# RF_Glow_Stick.net
KiCad netlist of a schematic drawn in EAGLE
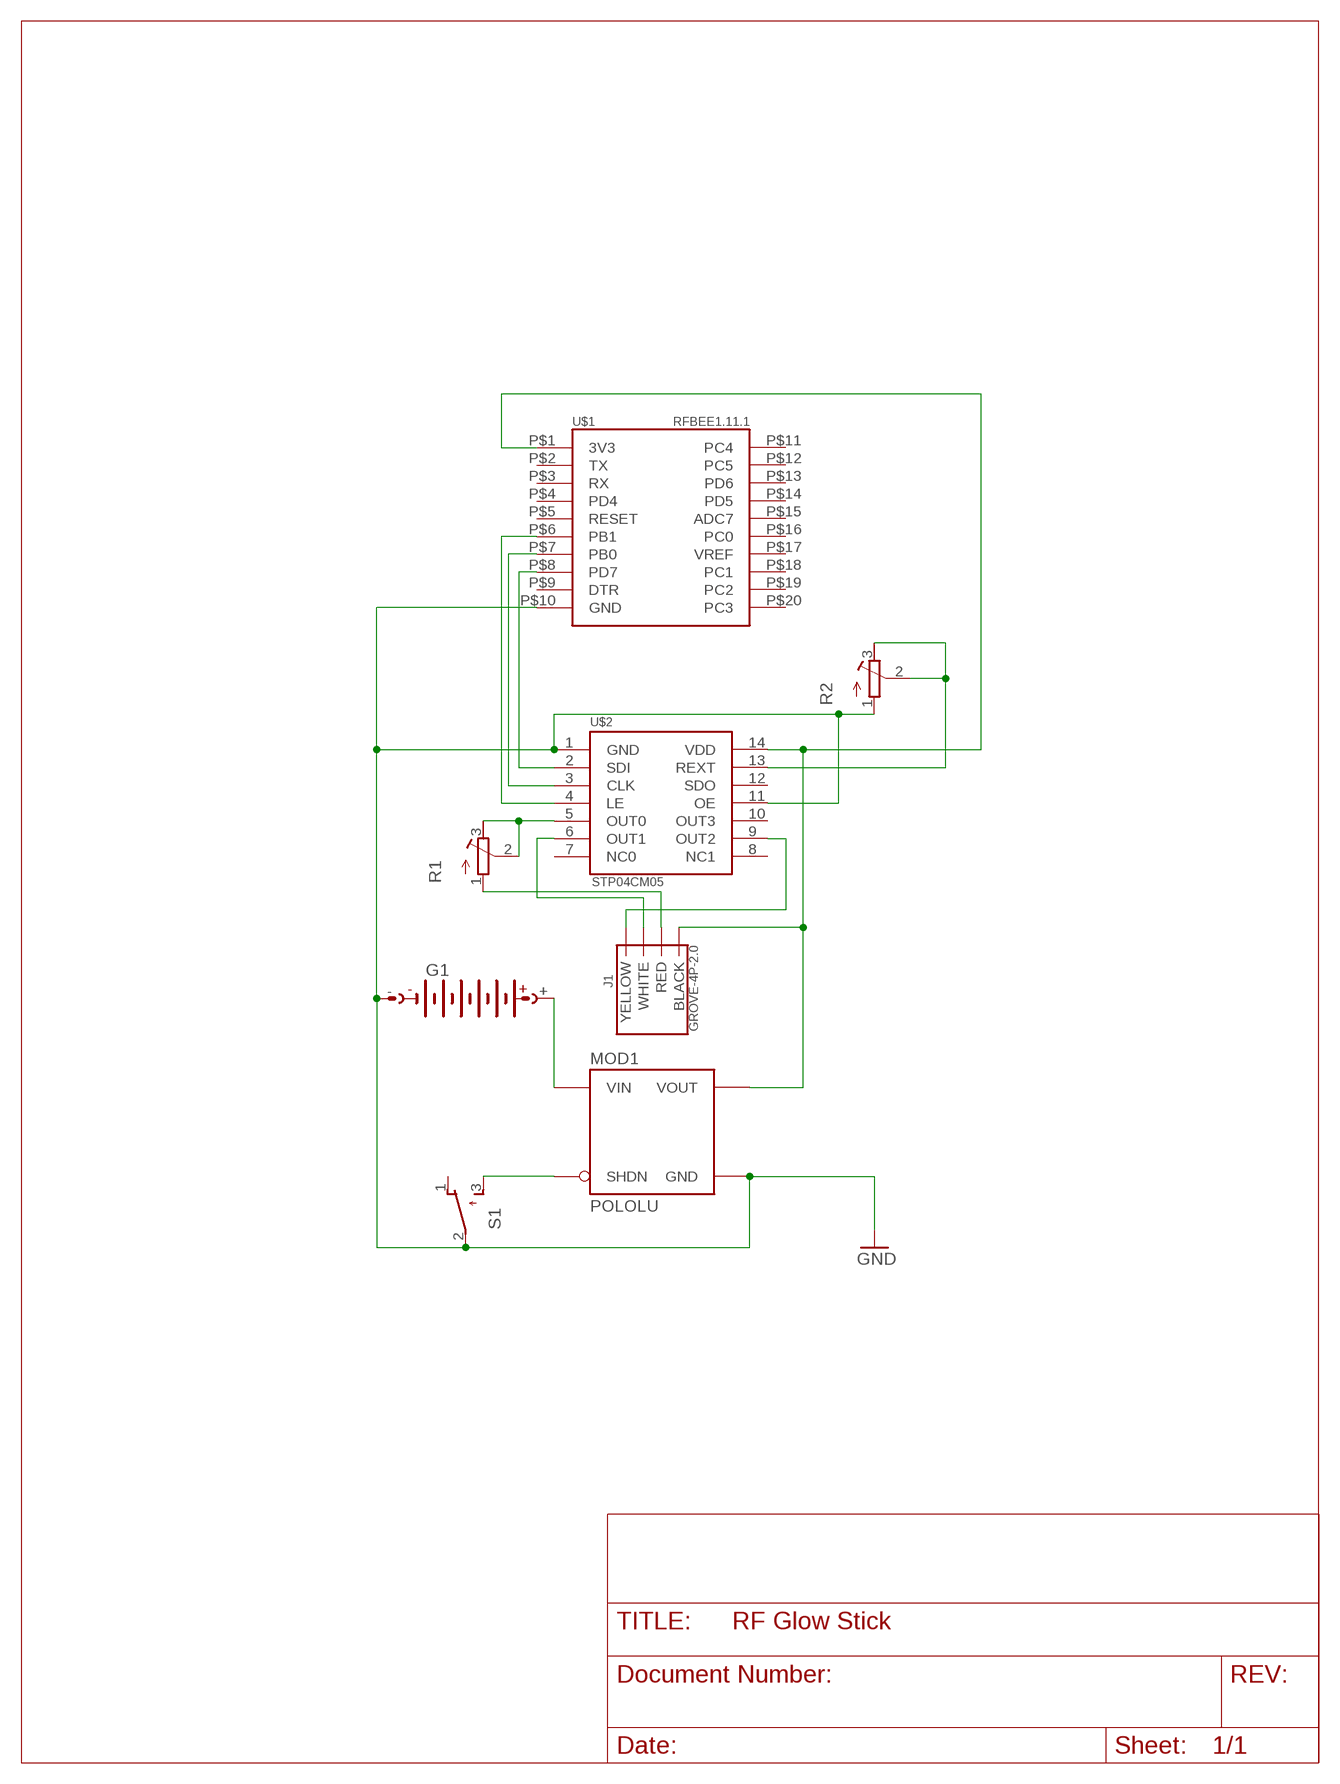
[diagram p0: schematic, sheet 1]

(export (version "E")
  (design (tool "Eeschema 10.0.6"))
  (components
    (comp (ref "G1")
      (value "AB9V")
      (footprint "eagle-import:AB9V")
      (libsource (lib "eagle-import") (part "AB9V"))
    )
    (comp (ref "J1")
      (value "GROVE-4P-2.0")
      (footprint "eagle-import:4P-2.0-90D")
      (libsource (lib "eagle-import") (part "GROVE-4P-2.0"))
    )
    (comp (ref "MOD1")
      (value "POLOLU")
      (footprint "eagle-import:POLOLU_REG09B")
      (libsource (lib "eagle-import") (part "POLOLU_REG09BV"))
    )
    (comp (ref "R1")
      (value "R-TRIMM3299W")
      (footprint "eagle-import:RTRIM3299W")
      (libsource (lib "eagle-import") (part "R-TRIMM3299W"))
    )
    (comp (ref "R2")
      (value "R-TRIMM3299W")
      (footprint "eagle-import:RTRIM3299W")
      (libsource (lib "eagle-import") (part "R-TRIMM3299W"))
    )
    (comp (ref "S1")
      (value "TL32PO")
      (footprint "eagle-import:TL3XPO")
      (libsource (lib "eagle-import") (part "TL32PO"))
    )
    (comp (ref "U$1")
      (value "RFBEE1.11.1")
      (footprint "eagle-import:RFBEE")
      (libsource (lib "eagle-import") (part "RFBEE1.11.1"))
    )
    (comp (ref "U$2")
      (value "STP04CM05")
      (footprint "eagle-import:DIL14")
      (libsource (lib "eagle-import") (part "STP04CM05STP04CM05"))
    )
  )
  (nets
    (net (code "1") (name "GND") (class "Default")
      (node (ref "G1") (pin "-") (pinfunction "-_-") (pintype "passive"))
      (node (ref "MOD1") (pin "G") (pinfunction "GND_G") (pintype "power_in"))
      (node (ref "R2") (pin "1") (pinfunction "A_1") (pintype "passive"))
      (node (ref "S1") (pin "2") (pinfunction "P_2") (pintype "passive"))
      (node (ref "U$1") (pin "P$10") (pinfunction "GND_P$10") (pintype "bidirectional"))
      (node (ref "U$2") (pin "1") (pinfunction "GND_1") (pintype "bidirectional"))
      (node (ref "U$2") (pin "11") (pinfunction "OE_11") (pintype "bidirectional"))
    )
    (net (code "2") (name "Net-(MOD1-SHDN)") (class "Default")
      (node (ref "MOD1") (pin "S") (pinfunction "SHDN_S") (pintype "input"))
      (node (ref "S1") (pin "3") (pinfunction "S_3") (pintype "passive"))
    )
    (net (code "3") (name "Net-(MOD1-VIN)") (class "Default")
      (node (ref "G1") (pin "+") (pinfunction "+_+") (pintype "passive"))
      (node (ref "MOD1") (pin "I") (pinfunction "VIN_I") (pintype "power_in"))
    )
    (net (code "4") (name "Net-(MOD1-VOUT)") (class "Default")
      (node (ref "J1") (pin "BLACK") (pinfunction "BLACK_BLACK") (pintype "bidirectional"))
      (node (ref "MOD1") (pin "O") (pinfunction "VOUT_O") (pintype "output"))
      (node (ref "U$1") (pin "P$1") (pinfunction "3V3_P$1") (pintype "bidirectional"))
      (node (ref "U$2") (pin "14") (pinfunction "VDD_14") (pintype "bidirectional"))
    )
    (net (code "5") (name "Net-(R1-A)") (class "Default")
      (node (ref "J1") (pin "RED") (pinfunction "RED_RED") (pintype "bidirectional"))
      (node (ref "R1") (pin "1") (pinfunction "A_1") (pintype "passive"))
    )
    (net (code "6") (name "Net-(R1-E)") (class "Default")
      (node (ref "R1") (pin "2") (pinfunction "S_2") (pintype "passive"))
      (node (ref "R1") (pin "3") (pinfunction "E_3") (pintype "passive"))
      (node (ref "U$2") (pin "5") (pinfunction "OUT0_5") (pintype "bidirectional"))
    )
    (net (code "7") (name "Net-(R2-E)") (class "Default")
      (node (ref "R2") (pin "2") (pinfunction "S_2") (pintype "passive"))
      (node (ref "R2") (pin "3") (pinfunction "E_3") (pintype "passive"))
      (node (ref "U$2") (pin "13") (pinfunction "REXT_13") (pintype "bidirectional"))
    )
    (net (code "8") (name "Net-(U$1-PB0)") (class "Default")
      (node (ref "U$1") (pin "P$7") (pinfunction "PB0_P$7") (pintype "bidirectional"))
      (node (ref "U$2") (pin "3") (pinfunction "CLK_3") (pintype "bidirectional"))
    )
    (net (code "9") (name "Net-(U$1-PB1)") (class "Default")
      (node (ref "U$1") (pin "P$6") (pinfunction "PB1_P$6") (pintype "bidirectional"))
      (node (ref "U$2") (pin "4") (pinfunction "LE_4") (pintype "bidirectional"))
    )
    (net (code "10") (name "Net-(U$1-PD7)") (class "Default")
      (node (ref "U$1") (pin "P$8") (pinfunction "PD7_P$8") (pintype "bidirectional"))
      (node (ref "U$2") (pin "2") (pinfunction "SDI_2") (pintype "bidirectional"))
    )
    (net (code "11") (name "Net-(U$2-OUT1)") (class "Default")
      (node (ref "J1") (pin "WHITE") (pinfunction "WHITE_WHITE") (pintype "bidirectional"))
      (node (ref "U$2") (pin "6") (pinfunction "OUT1_6") (pintype "bidirectional"))
    )
    (net (code "12") (name "Net-(U$2-OUT2)") (class "Default")
      (node (ref "J1") (pin "YELLOW") (pinfunction "YELLOW_YELLOW") (pintype "bidirectional"))
      (node (ref "U$2") (pin "9") (pinfunction "OUT2_9") (pintype "bidirectional"))
    )
    (net (code "13") (name "unconnected-(S1-O-Pad1)") (class "Default")
      (node (ref "S1") (pin "1") (pinfunction "O_1") (pintype "passive"))
    )
    (net (code "14") (name "unconnected-(U$1-ADC7-PadP$15)") (class "Default")
      (node (ref "U$1") (pin "P$15") (pinfunction "ADC7_P$15") (pintype "bidirectional"))
    )
    (net (code "15") (name "unconnected-(U$1-DTR-PadP$9)") (class "Default")
      (node (ref "U$1") (pin "P$9") (pinfunction "DTR_P$9") (pintype "bidirectional"))
    )
    (net (code "16") (name "unconnected-(U$1-PC0-PadP$16)") (class "Default")
      (node (ref "U$1") (pin "P$16") (pinfunction "PC0_P$16") (pintype "bidirectional"))
    )
    (net (code "17") (name "unconnected-(U$1-PC1-PadP$18)") (class "Default")
      (node (ref "U$1") (pin "P$18") (pinfunction "PC1_P$18") (pintype "bidirectional"))
    )
    (net (code "18") (name "unconnected-(U$1-PC2-PadP$19)") (class "Default")
      (node (ref "U$1") (pin "P$19") (pinfunction "PC2_P$19") (pintype "bidirectional"))
    )
    (net (code "19") (name "unconnected-(U$1-PC3-PadP$20)") (class "Default")
      (node (ref "U$1") (pin "P$20") (pinfunction "PC3_P$20") (pintype "bidirectional"))
    )
    (net (code "20") (name "unconnected-(U$1-PC4-PadP$11)") (class "Default")
      (node (ref "U$1") (pin "P$11") (pinfunction "PC4_P$11") (pintype "bidirectional"))
    )
    (net (code "21") (name "unconnected-(U$1-PC5-PadP$12)") (class "Default")
      (node (ref "U$1") (pin "P$12") (pinfunction "PC5_P$12") (pintype "bidirectional"))
    )
    (net (code "22") (name "unconnected-(U$1-PD4-PadP$4)") (class "Default")
      (node (ref "U$1") (pin "P$4") (pinfunction "PD4_P$4") (pintype "bidirectional"))
    )
    (net (code "23") (name "unconnected-(U$1-PD5-PadP$14)") (class "Default")
      (node (ref "U$1") (pin "P$14") (pinfunction "PD5_P$14") (pintype "bidirectional"))
    )
    (net (code "24") (name "unconnected-(U$1-PD6-PadP$13)") (class "Default")
      (node (ref "U$1") (pin "P$13") (pinfunction "PD6_P$13") (pintype "bidirectional"))
    )
    (net (code "25") (name "unconnected-(U$1-RESET-PadP$5)") (class "Default")
      (node (ref "U$1") (pin "P$5") (pinfunction "RESET_P$5") (pintype "bidirectional"))
    )
    (net (code "26") (name "unconnected-(U$1-RX-PadP$3)") (class "Default")
      (node (ref "U$1") (pin "P$3") (pinfunction "RX_P$3") (pintype "bidirectional"))
    )
    (net (code "27") (name "unconnected-(U$1-TX-PadP$2)") (class "Default")
      (node (ref "U$1") (pin "P$2") (pinfunction "TX_P$2") (pintype "bidirectional"))
    )
    (net (code "28") (name "unconnected-(U$1-VREF-PadP$17)") (class "Default")
      (node (ref "U$1") (pin "P$17") (pinfunction "VREF_P$17") (pintype "bidirectional"))
    )
    (net (code "29") (name "unconnected-(U$2-NC0-Pad7)") (class "Default")
      (node (ref "U$2") (pin "7") (pinfunction "NC0_7") (pintype "bidirectional"))
    )
    (net (code "30") (name "unconnected-(U$2-NC1-Pad8)") (class "Default")
      (node (ref "U$2") (pin "8") (pinfunction "NC1_8") (pintype "bidirectional"))
    )
    (net (code "31") (name "unconnected-(U$2-OUT3-Pad10)") (class "Default")
      (node (ref "U$2") (pin "10") (pinfunction "OUT3_10") (pintype "bidirectional"))
    )
    (net (code "32") (name "unconnected-(U$2-SDO-Pad12)") (class "Default")
      (node (ref "U$2") (pin "12") (pinfunction "SDO_12") (pintype "bidirectional"))
    )
  )
)
